# LightSensor.net
KiCad netlist of a schematic drawn in Altium Designer
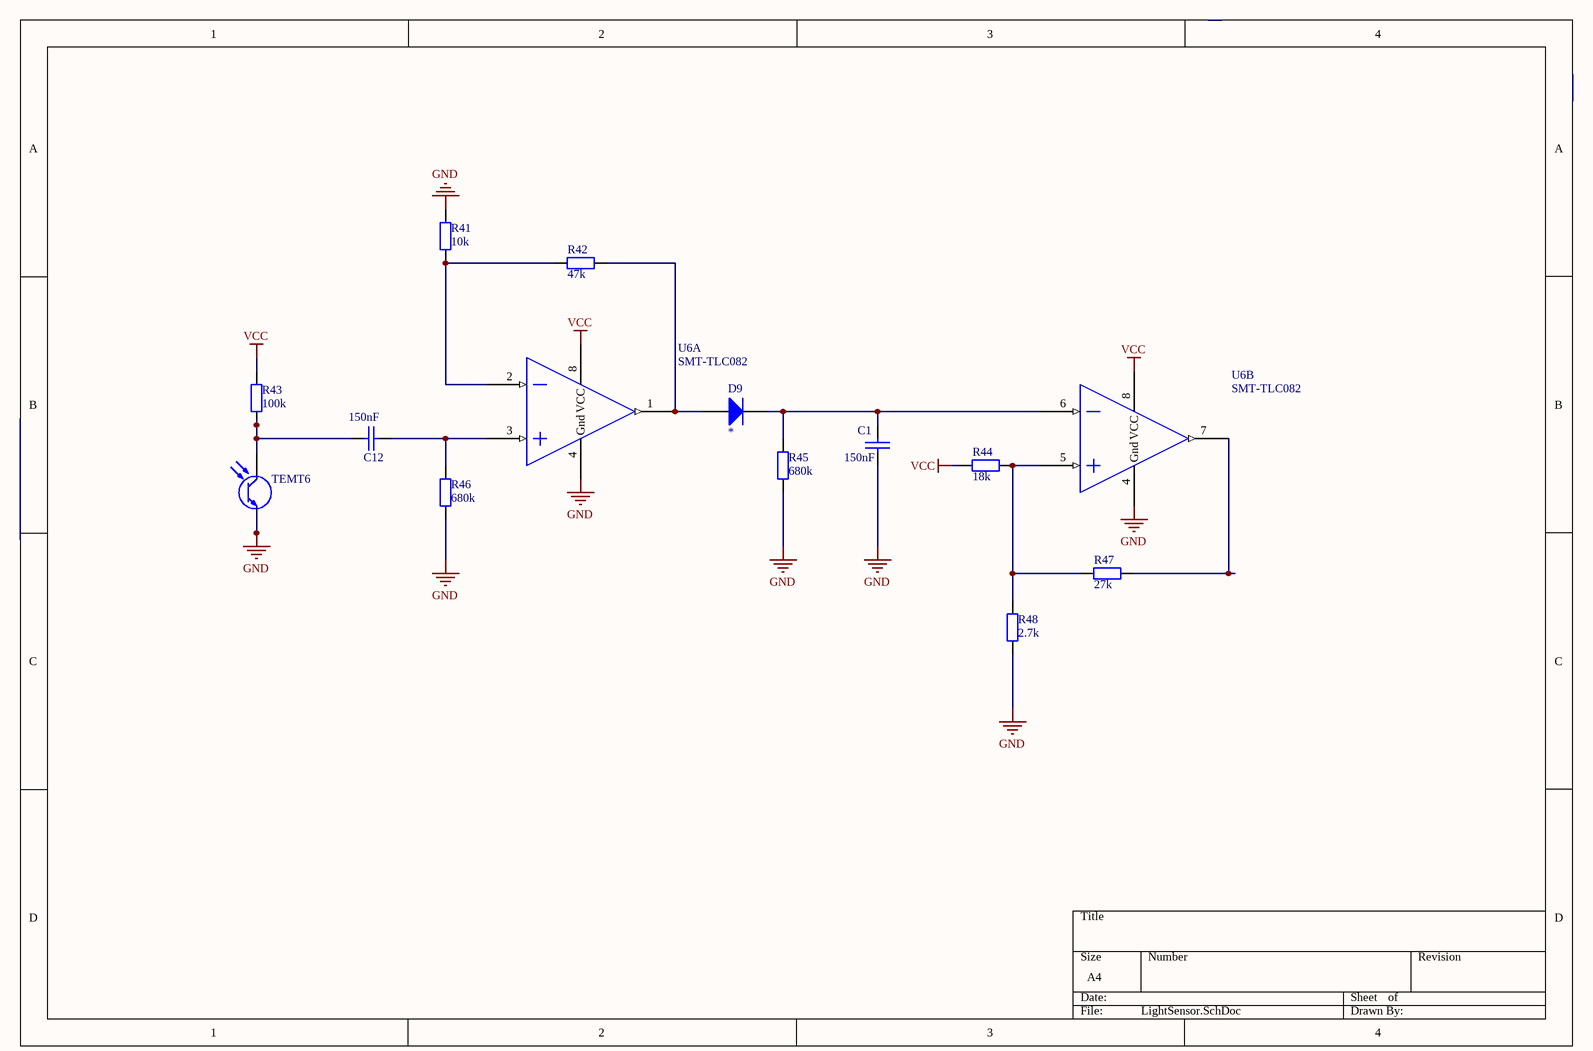
[diagram p0: LightSensor.SchDoc]

(export (version "E")
  (design (tool "Eeschema 10.0.6"))
  (components
    (comp (ref "C1")
      (value "150nF")
      (footprint "ECE-CAPC1608-0603SM")
      (description "CAP CER 150nF 25V X7R SM0603")
      (libsource (lib "EceParts") (part "Cap"))
    )
    (comp (ref "C12")
      (value "150nF")
      (footprint "ECE-CAPC1608-0603SM")
      (description "CAP CER 15nF 50V X7R SM0603")
      (libsource (lib "EceParts") (part "Cap"))
    )
    (comp (ref "D9")
      (value "*")
      (footprint "ece-DIODE0.4")
      (description "High Conductance Fast Diode")
      (fields
        (field (name "MANUFACTURER") "Fairchild Semiconductor")
        (field (name "PUBLISHER") "Altium Limited")
      )
      (libsource (lib "ece components") (part "DIODE"))
    )
    (comp (ref "R41")
      (value "10k")
      (footprint "RESC2012-0805SM")
      (description "SM resistor")
      (libsource (lib "ece components") (part "Res SM 0805"))
    )
    (comp (ref "R42")
      (value "47k")
      (footprint "RESC2012-0805SM")
      (description "SM resistor")
      (libsource (lib "") (part "Res SM 0805_1"))
    )
    (comp (ref "R43")
      (value "100k")
      (footprint "RESC2012-0805SM")
      (description "SM resistor")
      (libsource (lib "ece components") (part "Res SM 0805"))
    )
    (comp (ref "R44")
      (value "18k")
      (footprint "RESC2012-0805SM")
      (description "SM resistor")
      (libsource (lib "") (part "Res SM 0805_1"))
    )
    (comp (ref "R45")
      (value "680k")
      (footprint "RESC2012-0805SM")
      (description "SM resistor")
      (libsource (lib "ece components") (part "Res SM 0805"))
    )
    (comp (ref "R46")
      (value "680k")
      (footprint "RESC2012-0805SM")
      (description "SM resistor")
      (libsource (lib "ece components") (part "Res SM 0805"))
    )
    (comp (ref "R47")
      (value "27k")
      (footprint "RESC2012-0805SM")
      (description "SM resistor")
      (libsource (lib "") (part "Res SM 0805_1"))
    )
    (comp (ref "R48")
      (value "2.7k")
      (footprint "RESC2012-0805SM")
      (description "SM resistor")
      (libsource (lib "ece components") (part "Res SM 0805"))
    )
    (comp (ref "TEMT6")
      (value "TEMT6200")
      (footprint "ECE-SENSOR-0805SM")
      (description "LIGHT SENSOR TEMT6200 SM")
      (libsource (lib "EceParts") (part "TEMT6200"))
    )
    (comp (ref "U6") (value "SMT-TLC082") (footprint "SO-8") (libsource (lib "EE209") (part "SMT-TLC082")))
  )
  (nets
    (net (code "1") (name "GND") (class "Default")
      (node (ref "C1") (pin "2") (pinfunction "2_2") (pintype "passive"))
      (node (ref "R41") (pin "2") (pinfunction "2_2") (pintype "passive"))
      (node (ref "R45") (pin "1") (pinfunction "1_1") (pintype "passive"))
      (node (ref "R46") (pin "1") (pinfunction "1_1") (pintype "passive"))
      (node (ref "R48") (pin "1") (pinfunction "1_1") (pintype "passive"))
      (node (ref "TEMT6") (pin "1") (pinfunction "E_1") (pintype "passive"))
      (node (ref "U6") (pin "4") (pinfunction "Gnd_4") (pintype "power_in"))
    )
    (net (code "2") (name "Net-(D9-A)") (class "Default")
      (node (ref "D9") (pin "1") (pinfunction "A_1") (pintype "passive"))
      (node (ref "R42") (pin "1") (pinfunction "1_1") (pintype "passive"))
      (node (ref "U6") (pin "1") (pinfunction "OUT1_1") (pintype "output"))
    )
    (net (code "3") (name "Net-(D9-K)") (class "Default")
      (node (ref "C1") (pin "1") (pinfunction "1_1") (pintype "passive"))
      (node (ref "D9") (pin "2") (pinfunction "K_2") (pintype "passive"))
      (node (ref "R45") (pin "2") (pinfunction "2_2") (pintype "passive"))
      (node (ref "U6") (pin "6") (pinfunction "IN2(-)_6") (pintype "input"))
    )
    (net (code "4") (name "Net-(TEMT6-C)") (class "Default")
      (node (ref "C12") (pin "1") (pinfunction "1_1") (pintype "passive"))
      (node (ref "R43") (pin "1") (pinfunction "1_1") (pintype "passive"))
      (node (ref "TEMT6") (pin "2") (pinfunction "C_2") (pintype "passive"))
    )
    (net (code "5") (name "Net-(U6A-IN1(+))") (class "Default")
      (node (ref "C12") (pin "2") (pinfunction "2_2") (pintype "passive"))
      (node (ref "R46") (pin "2") (pinfunction "2_2") (pintype "passive"))
      (node (ref "U6") (pin "3") (pinfunction "IN1(+)_3") (pintype "input"))
    )
    (net (code "6") (name "Net-(U6A-IN1(-))") (class "Default")
      (node (ref "R41") (pin "1") (pinfunction "1_1") (pintype "passive"))
      (node (ref "R42") (pin "2") (pinfunction "2_2") (pintype "passive"))
      (node (ref "U6") (pin "2") (pinfunction "IN1(-)_2") (pintype "input"))
    )
    (net (code "7") (name "Net-(U6B-IN2(+))") (class "Default")
      (node (ref "R44") (pin "1") (pinfunction "1_1") (pintype "passive"))
      (node (ref "R47") (pin "2") (pinfunction "2_2") (pintype "passive"))
      (node (ref "R48") (pin "2") (pinfunction "2_2") (pintype "passive"))
      (node (ref "U6") (pin "5") (pinfunction "IN2(+)_5") (pintype "input"))
    )
    (net (code "8") (name "Net-(U6B-OUT2)") (class "Default")
      (node (ref "R47") (pin "1") (pinfunction "1_1") (pintype "passive"))
      (node (ref "U6") (pin "7") (pinfunction "OUT2_7") (pintype "output"))
    )
    (net (code "9") (name "VCC") (class "Default")
      (node (ref "R43") (pin "2") (pinfunction "2_2") (pintype "passive"))
      (node (ref "R44") (pin "2") (pinfunction "2_2") (pintype "passive"))
      (node (ref "U6") (pin "8") (pinfunction "VCC_8") (pintype "power_in"))
    )
  )
)
